# Power_Sheet.net
KiCad netlist of a schematic drawn in Altium Designer
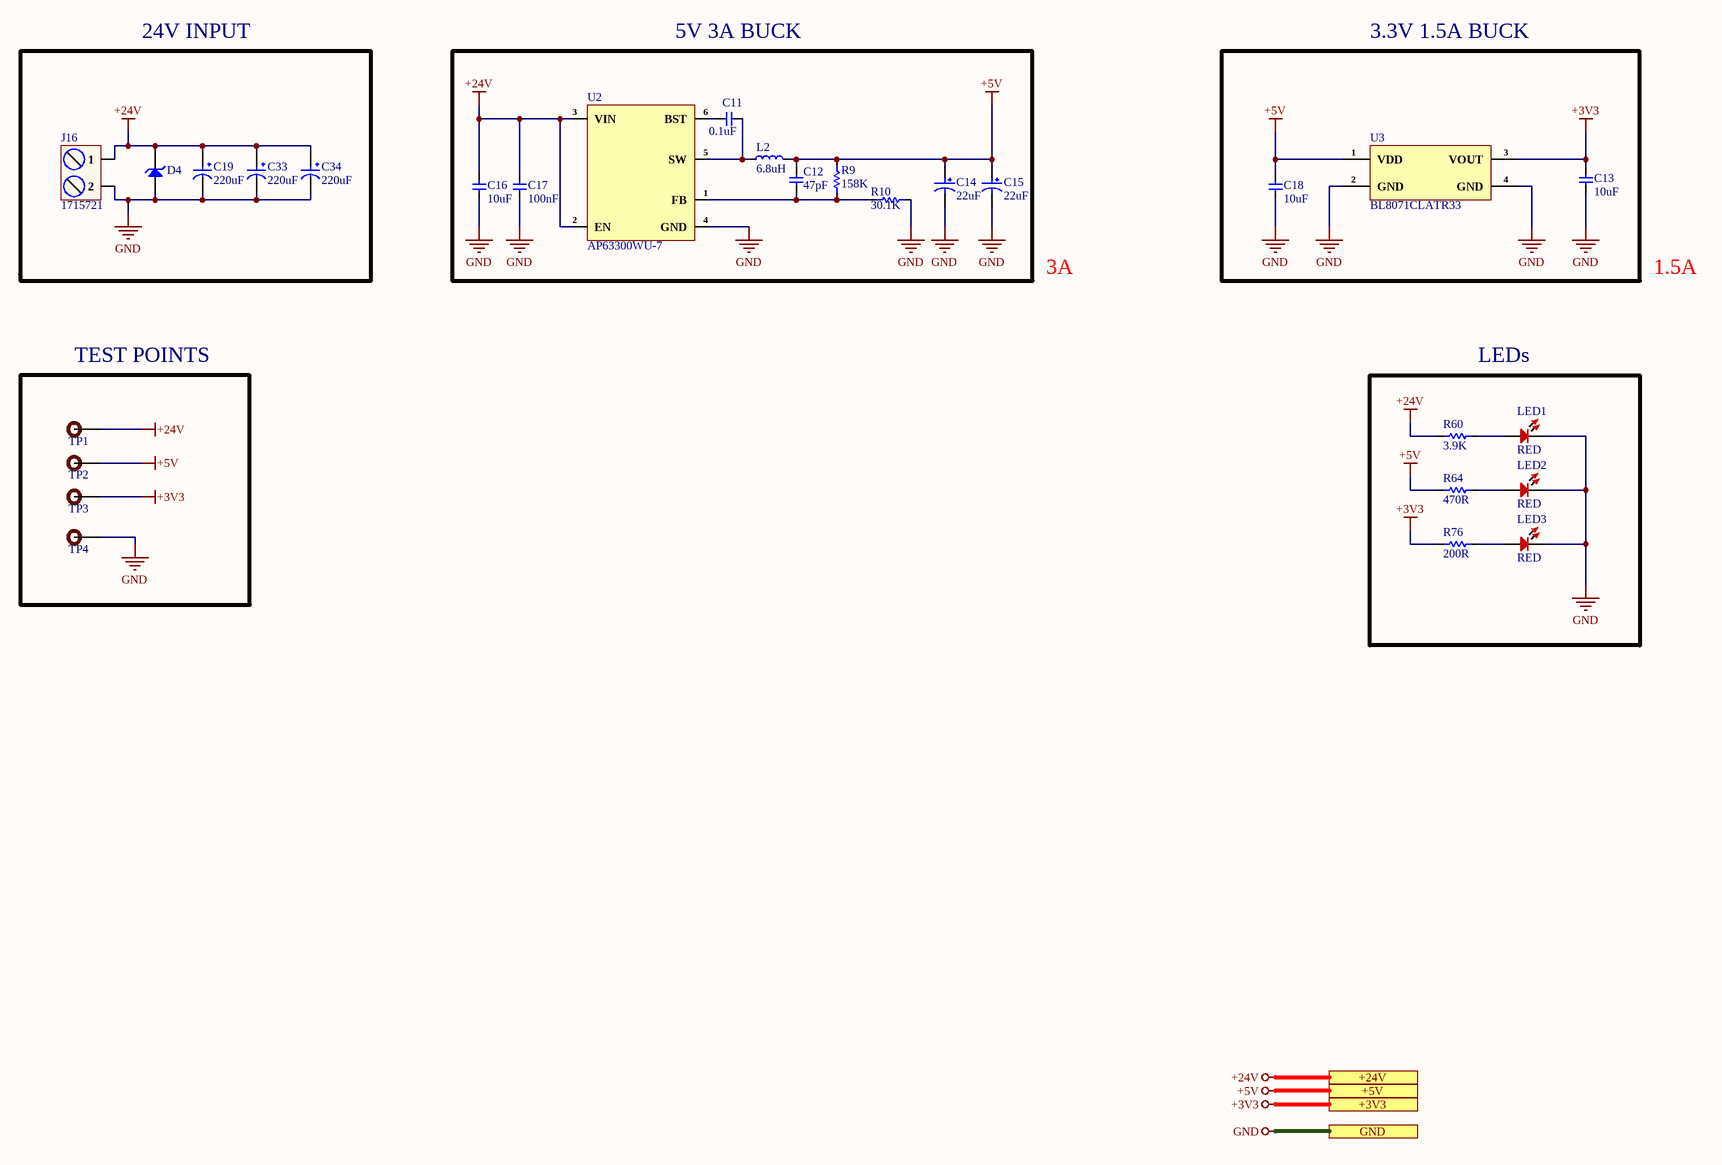
[diagram p0: Power_Sheet.SchDoc]

(export (version "E")
  (design (tool "Eeschema 10.0.6"))
  (components
    (comp (ref "C11")
      (value "0.1uF")
      (footprint "Cap-0402")
      (description "CAP CER 0.1UF 50V X5R 0402")
      (fields
        (field (name "MANUFACTURER") "TDK")
        (field (name "MANUFACTURER PART NUMBER") "C1005X5R1H104K050BB")
      )
      (libsource (lib "eSpark Libraries") (part "C1005X5R1H104K050BB"))
    )
    (comp (ref "C12")
      (value "47pF")
      (footprint "Cap-0402")
      (description "CAP CER 47PF 50V C0G/NP0 0402")
      (fields
        (field (name "MANUFACTURER") "Murata")
        (field (name "MANUFACTURER PART NUMBER") "GCM1555C1H470FA16D")
      )
      (libsource (lib "eSpark Libraries") (part "GCM1555C1H470FA16D"))
    )
    (comp (ref "C13")
      (value "10uF")
      (footprint "Cap-0603")
      (description "CAP CER 10UF 25V X5R 0603")
      (fields
        (field (name "MANUFACTURER") "TDK")
        (field (name "MANUFACTURER PART NUMBER") "C1608X5R1E106M080AC")
      )
      (libsource (lib "eSpark Libraries") (part "C1608X5R1E106M080AC"))
    )
    (comp (ref "C14")
      (value "22uF")
      (footprint "VKMD1652D220MV")
      (description "22uF 200V 320mA@100kHz ±20% SMD,D8xL16.5mm Aluminum Electrolytic Capacitors - SMD ROHS")
      (fields (field (name "MANUFACTURER") "Ymin") (field (name "MANUFACTURER PART NUMBER") "VKMD1652D220MV"))
      (libsource (lib "eSpark Libraries") (part "VKMD1652D220MV"))
    )
    (comp (ref "C15")
      (value "22uF")
      (footprint "VKMD1652D220MV")
      (description "22uF 200V 320mA@100kHz ±20% SMD,D8xL16.5mm Aluminum Electrolytic Capacitors - SMD ROHS")
      (fields (field (name "MANUFACTURER") "Ymin") (field (name "MANUFACTURER PART NUMBER") "VKMD1652D220MV"))
      (libsource (lib "eSpark Libraries") (part "VKMD1652D220MV"))
    )
    (comp (ref "C16")
      (value "10uF")
      (footprint "Cap-0603")
      (description "CAP CER 10UF 25V X5R 0603")
      (fields
        (field (name "MANUFACTURER") "TDK")
        (field (name "MANUFACTURER PART NUMBER") "C1608X5R1E106M080AC")
      )
      (libsource (lib "eSpark Libraries") (part "C1608X5R1E106M080AC"))
    )
    (comp (ref "C17")
      (value "100nF")
      (footprint "cap-0402")
      (description "CAP CER 0.1UF 50V X7R 0402")
      (fields
        (field (name "MANUFACTURER") "TDK")
        (field (name "MANUFACTURER PART NUMBER") "C1005X7R1H104KT000F")
      )
      (libsource (lib "eSpark Libraries") (part "C1005X7R1H104KT000F"))
    )
    (comp (ref "C18")
      (value "10uF")
      (footprint "Cap-0603")
      (description "CAP CER 10UF 25V X5R 0603")
      (fields
        (field (name "MANUFACTURER") "TDK")
        (field (name "MANUFACTURER PART NUMBER") "C1608X5R1E106M080AC")
      )
      (libsource (lib "eSpark Libraries") (part "C1608X5R1E106M080AC"))
    )
    (comp (ref "C19")
      (value "220uF")
      (footprint "UCD-220uF-10mmDia")
      (description "CAP ALUM 220UF 20% 50V SMD")
      (fields
        (field (name "MANUFACTURER") "Nichicon")
        (field (name "MANUFACTURER PART NUMBER") "UCD1H221MNL1GS")
      )
      (libsource (lib "eSpark Libraries") (part "UCD1H221MNL1GS"))
    )
    (comp (ref "C33")
      (value "220uF")
      (footprint "UCD-220uF-10mmDia")
      (description "CAP ALUM 220UF 20% 50V SMD")
      (fields
        (field (name "MANUFACTURER") "Nichicon")
        (field (name "MANUFACTURER PART NUMBER") "UCD1H221MNL1GS")
      )
      (libsource (lib "eSpark Libraries") (part "UCD1H221MNL1GS"))
    )
    (comp (ref "C34")
      (value "220uF")
      (footprint "UCD-220uF-10mmDia")
      (description "CAP ALUM 220UF 20% 50V SMD")
      (fields
        (field (name "MANUFACTURER") "Nichicon")
        (field (name "MANUFACTURER PART NUMBER") "UCD1H221MNL1GS")
      )
      (libsource (lib "eSpark Libraries") (part "UCD1H221MNL1GS"))
    )
    (comp (ref "D4")
      (value "SMBJ28A-13-F")
      (footprint "SMB_")
      (description "TVS DIODE 28VWM 45.4VC SMB")
      (fields (field (name "MANUFACTURER") "Diodes"))
      (libsource (lib "eSpark Libraries") (part "SMBJ28A-13-F"))
    )
    (comp (ref "J16")
      (value "1715721")
      (footprint "1715721")
      (description "TERM BLK 2P SIDE ENT 5.08MM PCB")
      (fields (field (name "MANUFACTURER") "Phoenix Contact"))
      (libsource (lib "eSpark Libraries") (part "1715721"))
    )
    (comp (ref "L2")
      (value "6.8uH")
      (footprint "LVC505040-6R8M-N_")
      (description "2.7A 6.8uH ±20% 50mΩ SMD Power Inductors ROHS")
      (fields
        (field (name "MANUFACTURER PART NUMBER") "LVC505040-6R8M-N")
        (field (name "MANUFACTURER") "Chlisin Elec")
      )
      (libsource (lib "eSpark Libraries") (part "LVC505040-6R8M-N"))
    )
    (comp (ref "LED1")
      (value "RED")
      (footprint "LED-0603")
      (description "RED LED 0603 Light Emitting Diodes")
      (fields
        (field (name "MANUFACTURER") "Foshan NationStar Optoelectronics")
        (field (name "MANUFACTURER PART NUMBER") "NCD0603R3")
      )
      (libsource (lib "eSpark Libraries") (part "NCD0603R3"))
    )
    (comp (ref "LED2")
      (value "RED")
      (footprint "LED-0603")
      (description "RED LED 0603 Light Emitting Diodes")
      (fields
        (field (name "MANUFACTURER") "Foshan NationStar Optoelectronics")
        (field (name "MANUFACTURER PART NUMBER") "NCD0603R3")
      )
      (libsource (lib "eSpark Libraries") (part "NCD0603R3"))
    )
    (comp (ref "LED3")
      (value "RED")
      (footprint "LED-0603")
      (description "RED LED 0603 Light Emitting Diodes")
      (fields
        (field (name "MANUFACTURER") "Foshan NationStar Optoelectronics")
        (field (name "MANUFACTURER PART NUMBER") "NCD0603R3")
      )
      (libsource (lib "eSpark Libraries") (part "NCD0603R3"))
    )
    (comp (ref "R9")
      (value "158K")
      (footprint "Res-0402")
      (description "RES 158K OHM 0.1% 1/16W 0402")
      (fields
        (field (name "MANUFACTURER") "Yageo")
        (field (name "MANUFACTURER PART NUMBER") "RT0402BRE07158KL")
      )
      (libsource (lib "eSpark Libraries") (part "RT0402BRE07158KL"))
    )
    (comp (ref "R10")
      (value "30.1K")
      (footprint "Res-0402")
      (description "RES SMD 30.1KOHM 0.1% 1/16W 0402")
      (fields
        (field (name "MANUFACTURER") "Yageo")
        (field (name "MANUFACTURER PART NUMBER") "RT0402BRD0730K1L")
      )
      (libsource (lib "eSpark Libraries") (part "RT0402BRD0730K1L"))
    )
    (comp (ref "R60")
      (value "3.9K")
      (footprint "Res-0402")
      (description "RES 3.9K OHM 1% 1/16W 0402")
      (fields
        (field (name "MANUFACTURER") "Yageo")
        (field (name "MANUFACTURER PART NUMBER") "RC0402FR-073K9L")
      )
      (libsource (lib "eSpark Libraries") (part "RC0402FR-073K9L"))
    )
    (comp (ref "R64")
      (value "470R")
      (footprint "Res-0402")
      (description "RES 470 OHM 1% 1/16W 0402")
      (fields
        (field (name "MANUFACTURER") "Yageo")
        (field (name "MANUFACTURER PART NUMBER") "RC0402FR-07470RL")
      )
      (libsource (lib "eSpark Libraries") (part "RC0402FR-07470RL"))
    )
    (comp (ref "R76")
      (value "200R")
      (footprint "Res-0402")
      (description "RES 200 OHM 1% 1/16W 0402")
      (fields
        (field (name "MANUFACTURER") "Yageo")
        (field (name "MANUFACTURER PART NUMBER") "RC0402FR-07200RL")
      )
      (libsource (lib "eSpark Libraries") (part "RC0402FR-07200RL"))
    )
    (comp (ref "TP1")
      (value "TEST POINT")
      (footprint "Test-point")
      (description "Test Point ON")
      (libsource (lib "eSpark Libraries") (part "TEST POINT"))
    )
    (comp (ref "TP2")
      (value "TEST POINT")
      (footprint "Test-point")
      (description "Test Point ON")
      (libsource (lib "eSpark Libraries") (part "TEST POINT"))
    )
    (comp (ref "TP3")
      (value "TEST POINT")
      (footprint "Test-point")
      (description "Test Point ON")
      (libsource (lib "eSpark Libraries") (part "TEST POINT"))
    )
    (comp (ref "TP4")
      (value "TEST POINT")
      (footprint "Test-point")
      (description "Test Point ON")
      (libsource (lib "eSpark Libraries") (part "TEST POINT"))
    )
    (comp (ref "U2")
      (value "AP63300WU-7")
      (footprint "SOT-23-6")
      (description "IC REG BUCK ADJ 3A TSOT26")
      (fields (field (name "MANUFACTURER") "Diodes") (field (name "LCSC PART NUMBER") "C2158012"))
      (libsource (lib "eSpark Libraries") (part "AP63300WU-7"))
    )
    (comp (ref "U3")
      (value "BL8071CLATR33")
      (footprint "SOT- 223")
      (description "70dB@(100Hz) 1.5A Fixed 3.3V~3.3V Positive 6V SOT-223 Linear Voltage Regulators (LDO) ROHS")
      (fields
        (field (name "MANUFACTURER") "BL(Shanghai Belling)")
        (field (name "LCSC PART NUMBER") "C401677")
      )
      (libsource (lib "eSpark Libraries") (part "BL8071CLATR33"))
    )
  )
  (nets
    (net (code "1") (name "+3V3") (class "Default")
      (node (ref "C13") (pin "2") (pinfunction "2_2") (pintype "passive"))
      (node (ref "R76") (pin "1") (pinfunction "1_1") (pintype "passive"))
      (node (ref "TP3") (pin "1") (pinfunction "1_1") (pintype "passive"))
      (node (ref "U3") (pin "3") (pinfunction "VOUT_3") (pintype "passive"))
    )
    (net (code "2") (name "+5V") (class "Default")
      (node (ref "C12") (pin "2") (pinfunction "2_2") (pintype "passive"))
      (node (ref "C14") (pin "1") (pintype "passive"))
      (node (ref "C15") (pin "1") (pintype "passive"))
      (node (ref "C18") (pin "2") (pinfunction "2_2") (pintype "passive"))
      (node (ref "L2") (pin "2") (pinfunction "2_2") (pintype "passive"))
      (node (ref "R64") (pin "1") (pinfunction "1_1") (pintype "passive"))
      (node (ref "R9") (pin "2") (pinfunction "2_2") (pintype "passive"))
      (node (ref "TP2") (pin "1") (pinfunction "1_1") (pintype "passive"))
      (node (ref "U3") (pin "1") (pinfunction "VDD_1") (pintype "passive"))
    )
    (net (code "3") (name "+24V") (class "Default")
      (node (ref "C16") (pin "2") (pinfunction "2_2") (pintype "passive"))
      (node (ref "C17") (pin "2") (pinfunction "2_2") (pintype "passive"))
      (node (ref "C19") (pin "1") (pinfunction "1_1") (pintype "passive"))
      (node (ref "C33") (pin "1") (pinfunction "1_1") (pintype "passive"))
      (node (ref "C34") (pin "1") (pinfunction "1_1") (pintype "passive"))
      (node (ref "D4") (pin "2") (pinfunction "K_2") (pintype "passive"))
      (node (ref "J16") (pin "1") (pinfunction "1_1") (pintype "passive"))
      (node (ref "R60") (pin "1") (pinfunction "1_1") (pintype "passive"))
      (node (ref "TP1") (pin "1") (pinfunction "1_1") (pintype "passive"))
      (node (ref "U2") (pin "2") (pinfunction "EN_2") (pintype "passive"))
      (node (ref "U2") (pin "3") (pinfunction "VIN_3") (pintype "passive"))
    )
    (net (code "4") (name "GND") (class "Default")
      (node (ref "C13") (pin "1") (pinfunction "1_1") (pintype "passive"))
      (node (ref "C14") (pin "2") (pintype "passive"))
      (node (ref "C15") (pin "2") (pintype "passive"))
      (node (ref "C16") (pin "1") (pinfunction "1_1") (pintype "passive"))
      (node (ref "C17") (pin "1") (pinfunction "1_1") (pintype "passive"))
      (node (ref "C18") (pin "1") (pinfunction "1_1") (pintype "passive"))
      (node (ref "C19") (pin "2") (pinfunction "2_2") (pintype "passive"))
      (node (ref "C33") (pin "2") (pinfunction "2_2") (pintype "passive"))
      (node (ref "C34") (pin "2") (pinfunction "2_2") (pintype "passive"))
      (node (ref "D4") (pin "1") (pinfunction "A_1") (pintype "passive"))
      (node (ref "J16") (pin "2") (pinfunction "2_2") (pintype "passive"))
      (node (ref "LED1") (pin "2") (pinfunction "2_2") (pintype "passive"))
      (node (ref "LED2") (pin "2") (pinfunction "2_2") (pintype "passive"))
      (node (ref "LED3") (pin "2") (pinfunction "2_2") (pintype "passive"))
      (node (ref "R10") (pin "2") (pinfunction "2_2") (pintype "passive"))
      (node (ref "TP4") (pin "1") (pinfunction "1_1") (pintype "passive"))
      (node (ref "U2") (pin "4") (pinfunction "GND_4") (pintype "passive"))
      (node (ref "U3") (pin "2") (pinfunction "GND_2") (pintype "passive"))
      (node (ref "U3") (pin "4") (pinfunction "GND_4") (pintype "passive"))
    )
    (net (code "5") (name "Net-(LED1-Pad1)") (class "Default")
      (node (ref "LED1") (pin "1") (pinfunction "1_1") (pintype "passive"))
      (node (ref "R60") (pin "2") (pinfunction "2_2") (pintype "passive"))
    )
    (net (code "6") (name "Net-(LED2-Pad1)") (class "Default")
      (node (ref "LED2") (pin "1") (pinfunction "1_1") (pintype "passive"))
      (node (ref "R64") (pin "2") (pinfunction "2_2") (pintype "passive"))
    )
    (net (code "7") (name "Net-(LED3-Pad1)") (class "Default")
      (node (ref "LED3") (pin "1") (pinfunction "1_1") (pintype "passive"))
      (node (ref "R76") (pin "2") (pinfunction "2_2") (pintype "passive"))
    )
    (net (code "8") (name "Net-(U2-BST)") (class "Default")
      (node (ref "C11") (pin "2") (pinfunction "2_2") (pintype "passive"))
      (node (ref "U2") (pin "6") (pinfunction "BST_6") (pintype "passive"))
    )
    (net (code "9") (name "Net-(U2-FB)") (class "Default")
      (node (ref "C12") (pin "1") (pinfunction "1_1") (pintype "passive"))
      (node (ref "R10") (pin "1") (pinfunction "1_1") (pintype "passive"))
      (node (ref "R9") (pin "1") (pinfunction "1_1") (pintype "passive"))
      (node (ref "U2") (pin "1") (pinfunction "FB_1") (pintype "passive"))
    )
    (net (code "10") (name "Net-(U2-SW)") (class "Default")
      (node (ref "C11") (pin "1") (pinfunction "1_1") (pintype "passive"))
      (node (ref "L2") (pin "1") (pinfunction "1_1") (pintype "passive"))
      (node (ref "U2") (pin "5") (pinfunction "SW_5") (pintype "passive"))
    )
  )
)
